# Physio_v1_0.net
KiCad netlist of a schematic drawn in EAGLE
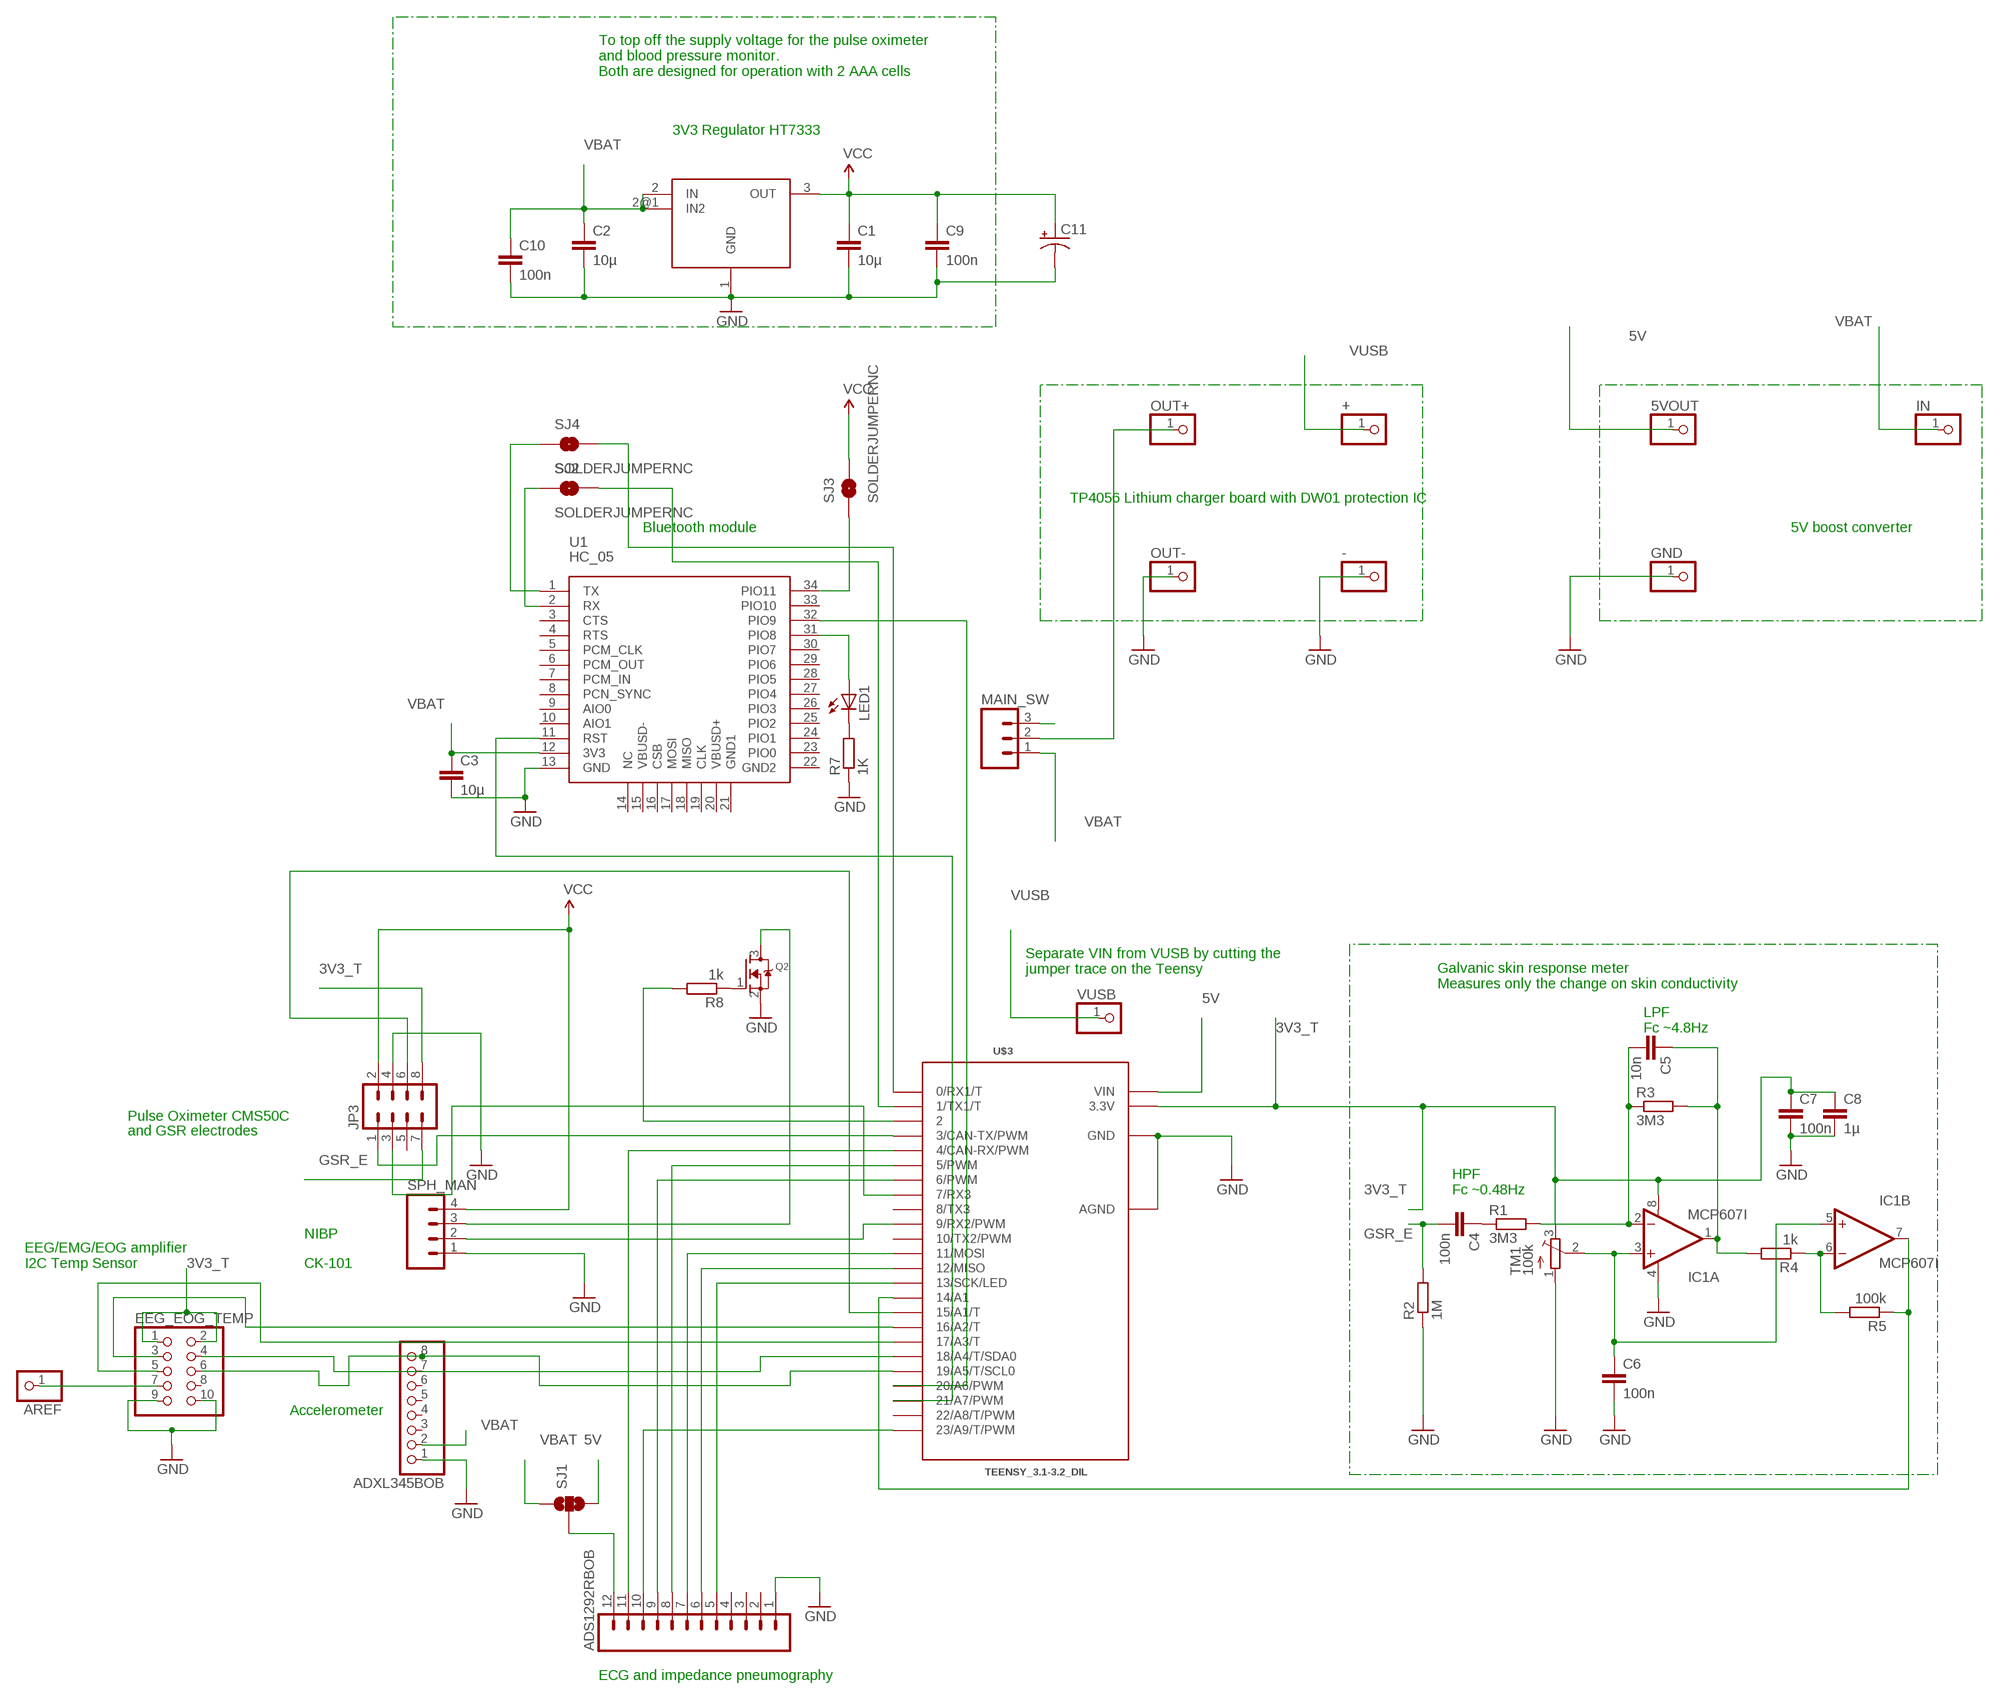
[diagram p0: schematic, sheet 1]

(export (version "E")
  (design (tool "Eeschema 10.0.6"))
  (components
    (comp (ref "+")
      (value "PINHD-1X1")
      (footprint "eagle-import:1X01")
      (libsource (lib "eagle-import") (part "PINHD-1X1"))
    )
    (comp (ref "-")
      (value "PINHD-1X1")
      (footprint "eagle-import:1X01")
      (libsource (lib "eagle-import") (part "PINHD-1X1"))
    )
    (comp (ref "5VOUT")
      (value "PINHD-1X1")
      (footprint "eagle-import:1X01")
      (libsource (lib "eagle-import") (part "PINHD-1X1"))
    )
    (comp (ref "ADS1292RBOB")
      (value "M12PTH")
      (footprint "eagle-import:1X12")
      (libsource (lib "eagle-import") (part "M12PTH"))
    )
    (comp (ref "ADXL345BOB")
      (value "PINHD-1X8CLEANBIG")
      (footprint "eagle-import:1X08-CLEANBIG")
      (libsource (lib "eagle-import") (part "PINHD-1X8CLEANBIG"))
    )
    (comp (ref "AREF")
      (value "PINHD-1X1")
      (footprint "eagle-import:1X01")
      (libsource (lib "eagle-import") (part "pinhead_PINHD-1X1"))
    )
    (comp (ref "C1")
      (value "10µ")
      (footprint "eagle-import:C0805K")
      (libsource (lib "eagle-import") (part "C-EUC0805K"))
    )
    (comp (ref "C2")
      (value "10µ")
      (footprint "eagle-import:C0805K")
      (libsource (lib "eagle-import") (part "C-EUC0805K"))
    )
    (comp (ref "C3")
      (value "10µ")
      (footprint "eagle-import:C0805K")
      (libsource (lib "eagle-import") (part "C-EUC0805K"))
    )
    (comp (ref "C4")
      (value "100n")
      (footprint "eagle-import:C0603K")
      (libsource (lib "eagle-import") (part "C-EUC0603K"))
    )
    (comp (ref "C5")
      (value "10n")
      (footprint "eagle-import:C0603K")
      (libsource (lib "eagle-import") (part "C-EUC0603K"))
    )
    (comp (ref "C6")
      (value "100n")
      (footprint "eagle-import:C0603K")
      (libsource (lib "eagle-import") (part "C-EUC0603K"))
    )
    (comp (ref "C7")
      (value "100n")
      (footprint "eagle-import:C0603K")
      (libsource (lib "eagle-import") (part "C-EUC0603K"))
    )
    (comp (ref "C8")
      (value "1µ")
      (footprint "eagle-import:C0603K")
      (libsource (lib "eagle-import") (part "C-EUC0603K"))
    )
    (comp (ref "C9")
      (value "100n")
      (footprint "eagle-import:C0603K")
      (libsource (lib "eagle-import") (part "C-EUC0603K"))
    )
    (comp (ref "C10")
      (value "100n")
      (footprint "eagle-import:C0603K")
      (libsource (lib "eagle-import") (part "C-EUC0603K"))
    )
    (comp (ref "C11")
      (value "CAP_POL7343")
      (footprint "eagle-import:EIA7343")
      (libsource (lib "eagle-import") (part "CAP_POL7343"))
    )
    (comp (ref "EEG_EOG_TEMP")
      (value "PINHD-2X5/90")
      (footprint "eagle-import:2X05_90")
      (libsource (lib "eagle-import") (part "PINHD-2X5/90"))
    )
    (comp (ref "GND")
      (value "PINHD-1X1")
      (footprint "eagle-import:1X01")
      (libsource (lib "eagle-import") (part "PINHD-1X1"))
    )
    (comp (ref "IC1")
      (value "MCP607I")
      (footprint "eagle-import:SO08")
      (libsource (lib "eagle-import") (part "OPAMP-DUALU"))
    )
    (comp (ref "IN")
      (value "PINHD-1X1")
      (footprint "eagle-import:1X01")
      (libsource (lib "eagle-import") (part "PINHD-1X1"))
    )
    (comp (ref "JP3")
      (value "M04X2")
      (footprint "eagle-import:2X4")
      (libsource (lib "eagle-import") (part "M04X2"))
    )
    (comp (ref "LED1")
      (value "LEDCHIP-LED0805")
      (footprint "eagle-import:CHIP-LED0805")
      (libsource (lib "eagle-import") (part "LEDCHIP-LED0805"))
    )
    (comp (ref "MAIN_SW")
      (value "M03PTH")
      (footprint "eagle-import:1X03")
      (libsource (lib "eagle-import") (part "M03PTH"))
    )
    (comp (ref "OUT+")
      (value "PINHD-1X1")
      (footprint "eagle-import:1X01")
      (libsource (lib "eagle-import") (part "PINHD-1X1"))
    )
    (comp (ref "OUT-")
      (value "PINHD-1X1")
      (footprint "eagle-import:1X01")
      (libsource (lib "eagle-import") (part "PINHD-1X1"))
    )
    (comp (ref "Q2")
      (value "MOSFET-NREFLOW")
      (footprint "eagle-import:SOT23")
      (libsource (lib "eagle-import") (part "MOSFET-NREFLOW"))
    )
    (comp (ref "R1")
      (value "3M3")
      (footprint "eagle-import:R0603")
      (libsource (lib "eagle-import") (part "R-EU_R0603"))
    )
    (comp (ref "R2")
      (value "1M")
      (footprint "eagle-import:R0603")
      (libsource (lib "eagle-import") (part "R-EU_R0603"))
    )
    (comp (ref "R3")
      (value "3M3")
      (footprint "eagle-import:R0603")
      (libsource (lib "eagle-import") (part "R-EU_R0603"))
    )
    (comp (ref "R4")
      (value "1k")
      (footprint "eagle-import:R0603")
      (libsource (lib "eagle-import") (part "R-EU_R0603"))
    )
    (comp (ref "R5")
      (value "100k")
      (footprint "eagle-import:R0603")
      (libsource (lib "eagle-import") (part "R-EU_R0603"))
    )
    (comp (ref "R7")
      (value "1K")
      (footprint "eagle-import:R0603")
      (libsource (lib "eagle-import") (part "R-EU_R0603"))
    )
    (comp (ref "R8")
      (value "1k")
      (footprint "eagle-import:R0603")
      (libsource (lib "eagle-import") (part "R-EU_R0603"))
    )
    (comp (ref "SJ1")
      (value "SOLDERJUMPER_2WAY-OLDT")
      (footprint "eagle-import:SJ_2")
      (libsource (lib "eagle-import") (part "SOLDERJUMPER_2WAY-OLDT"))
    )
    (comp (ref "SJ2")
      (value "SOLDERJUMPERNC")
      (footprint "eagle-import:SJ_2S")
      (libsource (lib "eagle-import") (part "SOLDERJUMPERNC"))
    )
    (comp (ref "SJ3")
      (value "SOLDERJUMPERNC")
      (footprint "eagle-import:SJ_2S")
      (libsource (lib "eagle-import") (part "SOLDERJUMPERNC"))
    )
    (comp (ref "SJ4")
      (value "SOLDERJUMPERNC")
      (footprint "eagle-import:SJ_2S")
      (libsource (lib "eagle-import") (part "SOLDERJUMPERNC"))
    )
    (comp (ref "SPH_MAN")
      (value "M04PTH")
      (footprint "eagle-import:1X04")
      (libsource (lib "eagle-import") (part "M04PTH"))
    )
    (comp (ref "TM1")
      (value "100k")
      (footprint "eagle-import:TC33X")
      (libsource (lib "eagle-import") (part "TRIMPOTTC33X"))
    )
    (comp (ref "U$2")
      (value "HT7333")
      (footprint "eagle-import:SOT89")
      (libsource (lib "eagle-import") (part "HT7333"))
    )
    (comp (ref "U$3")
      (value "TEENSY_3.1-3.2_DIL")
      (footprint "eagle-import:TEENSY_3.0-3.2&LC_DIL")
      (libsource (lib "eagle-import") (part "TEENSY_3.1-3.2_DIL"))
    )
    (comp (ref "U1")
      (value "HC_05")
      (footprint "eagle-import:BLUETOOTH_SMD")
      (libsource (lib "eagle-import") (part "HC_05"))
    )
    (comp (ref "VUSB")
      (value "PINHD-1X1")
      (footprint "eagle-import:1X01")
      (libsource (lib "eagle-import") (part "PINHD-1X1"))
    )
  )
  (nets
    (net (code "1") (name "/3V3_T") (class "Default")
      (node (ref "C7") (pin "1") (pinfunction "1_1") (pintype "passive"))
      (node (ref "C8") (pin "1") (pinfunction "1_1") (pintype "passive"))
      (node (ref "EEG_EOG_TEMP") (pin "1") (pinfunction "1_1") (pintype "passive"))
      (node (ref "EEG_EOG_TEMP") (pin "2") (pinfunction "2_2") (pintype "passive"))
      (node (ref "IC1") (pin "8") (pinfunction "V+_8") (pintype "power_in"))
      (node (ref "JP3") (pin "8") (pinfunction "8_8") (pintype "passive"))
      (node (ref "TM1") (pin "3") (pinfunction "E_3") (pintype "passive"))
      (node (ref "U$3") (pin "3.3V") (pinfunction "3.3V_3.3V") (pintype "power_in"))
    )
    (net (code "2") (name "/5V") (class "Default")
      (node (ref "5VOUT") (pin "1") (pinfunction "1_1") (pintype "passive"))
      (node (ref "SJ1") (pin "3") (pinfunction "3_3") (pintype "passive"))
      (node (ref "U$3") (pin "VIN") (pinfunction "VIN_VIN") (pintype "power_in"))
    )
    (net (code "3") (name "/GSR_E") (class "Default")
      (node (ref "C4") (pin "2") (pinfunction "2_2") (pintype "passive"))
      (node (ref "JP3") (pin "7") (pinfunction "7_7") (pintype "passive"))
      (node (ref "R2") (pin "2") (pinfunction "2_2") (pintype "passive"))
    )
    (net (code "5") (name "/VBAT") (class "Default")
      (node (ref "ADXL345BOB") (pin "2") (pinfunction "2_2") (pintype "passive"))
      (node (ref "C10") (pin "1") (pinfunction "1_1") (pintype "passive"))
      (node (ref "C2") (pin "1") (pinfunction "1_1") (pintype "passive"))
      (node (ref "C3") (pin "1") (pinfunction "1_1") (pintype "passive"))
      (node (ref "IN") (pin "1") (pinfunction "1_1") (pintype "passive"))
      (node (ref "MAIN_SW") (pin "1") (pinfunction "1_1") (pintype "passive"))
      (node (ref "SJ1") (pin "1") (pinfunction "1_1") (pintype "passive"))
      (node (ref "U$2") (pin "2") (pinfunction "IN_2") (pintype "bidirectional"))
      (node (ref "U$2") (pin "2@1") (pinfunction "IN2_2@1") (pintype "bidirectional"))
      (node (ref "U1") (pin "12") (pinfunction "3V3_12") (pintype "bidirectional"))
    )
    (net (code "6") (name "/VUSB") (class "Default")
      (node (ref "+") (pin "1") (pinfunction "1_1") (pintype "passive"))
      (node (ref "VUSB") (pin "1") (pinfunction "1_1") (pintype "passive"))
    )
    (net (code "7") (name "GND") (class "Default")
      (node (ref "-") (pin "1") (pinfunction "1_1") (pintype "passive"))
      (node (ref "ADS1292RBOB") (pin "1") (pinfunction "1_1") (pintype "passive"))
      (node (ref "ADXL345BOB") (pin "1") (pinfunction "1_1") (pintype "passive"))
      (node (ref "C1") (pin "2") (pinfunction "2_2") (pintype "passive"))
      (node (ref "C10") (pin "2") (pinfunction "2_2") (pintype "passive"))
      (node (ref "C11") (pin "C") (pinfunction "-_C") (pintype "passive"))
      (node (ref "C2") (pin "2") (pinfunction "2_2") (pintype "passive"))
      (node (ref "C3") (pin "2") (pinfunction "2_2") (pintype "passive"))
      (node (ref "C6") (pin "2") (pinfunction "2_2") (pintype "passive"))
      (node (ref "C7") (pin "2") (pinfunction "2_2") (pintype "passive"))
      (node (ref "C8") (pin "2") (pinfunction "2_2") (pintype "passive"))
      (node (ref "C9") (pin "2") (pinfunction "2_2") (pintype "passive"))
      (node (ref "EEG_EOG_TEMP") (pin "10") (pinfunction "10_10") (pintype "passive"))
      (node (ref "EEG_EOG_TEMP") (pin "9") (pinfunction "9_9") (pintype "passive"))
      (node (ref "GND") (pin "1") (pinfunction "1_1") (pintype "passive"))
      (node (ref "IC1") (pin "4") (pinfunction "V-_4") (pintype "power_in"))
      (node (ref "JP3") (pin "4") (pinfunction "4_4") (pintype "passive"))
      (node (ref "OUT-") (pin "1") (pinfunction "1_1") (pintype "passive"))
      (node (ref "Q2") (pin "2") (pinfunction "S_2") (pintype "bidirectional"))
      (node (ref "R2") (pin "1") (pinfunction "1_1") (pintype "passive"))
      (node (ref "R7") (pin "1") (pinfunction "1_1") (pintype "passive"))
      (node (ref "SPH_MAN") (pin "1") (pinfunction "1_1") (pintype "passive"))
      (node (ref "TM1") (pin "1") (pinfunction "A_1") (pintype "passive"))
      (node (ref "U$2") (pin "1") (pinfunction "GND_1") (pintype "bidirectional"))
      (node (ref "U$3") (pin "AGND") (pinfunction "AGND_AGND") (pintype "power_in"))
      (node (ref "U$3") (pin "GND") (pinfunction "GND_GND") (pintype "power_in"))
      (node (ref "U1") (pin "13") (pinfunction "GND_13") (pintype "bidirectional"))
    )
    (net (code "8") (name "Net-(ADS1292RBOB-Pad12)") (class "Default")
      (node (ref "ADS1292RBOB") (pin "12") (pinfunction "12_12") (pintype "passive"))
      (node (ref "SJ1") (pin "2") (pinfunction "2_2") (pintype "passive"))
    )
    (net (code "9") (name "Net-(AREF-Pad1)") (class "Default")
      (node (ref "AREF") (pin "1") (pinfunction "1_1") (pintype "passive"))
      (node (ref "EEG_EOG_TEMP") (pin "7") (pinfunction "7_7") (pintype "passive"))
    )
    (net (code "10") (name "Net-(C4-Pad1)") (class "Default")
      (node (ref "C4") (pin "1") (pinfunction "1_1") (pintype "passive"))
      (node (ref "R1") (pin "1") (pinfunction "1_1") (pintype "passive"))
    )
    (net (code "11") (name "Net-(IC1A-+IN)") (class "Default")
      (node (ref "C6") (pin "1") (pinfunction "1_1") (pintype "passive"))
      (node (ref "IC1") (pin "3") (pinfunction "+IN_3") (pintype "input"))
      (node (ref "IC1") (pin "5") (pinfunction "+IN_5") (pintype "input"))
      (node (ref "TM1") (pin "2") (pinfunction "S_2") (pintype "passive"))
    )
    (net (code "12") (name "Net-(IC1A--IN)") (class "Default")
      (node (ref "C5") (pin "2") (pinfunction "2_2") (pintype "passive"))
      (node (ref "IC1") (pin "2") (pinfunction "-IN_2") (pintype "input"))
      (node (ref "R1") (pin "2") (pinfunction "2_2") (pintype "passive"))
      (node (ref "R3") (pin "1") (pinfunction "1_1") (pintype "passive"))
    )
    (net (code "13") (name "Net-(IC1A-OUT)") (class "Default")
      (node (ref "C5") (pin "1") (pinfunction "1_1") (pintype "passive"))
      (node (ref "IC1") (pin "1") (pinfunction "OUT_1") (pintype "output"))
      (node (ref "R3") (pin "2") (pinfunction "2_2") (pintype "passive"))
      (node (ref "R4") (pin "2") (pinfunction "2_2") (pintype "passive"))
    )
    (net (code "14") (name "Net-(IC1B--IN)") (class "Default")
      (node (ref "IC1") (pin "6") (pinfunction "-IN_6") (pintype "input"))
      (node (ref "R4") (pin "1") (pinfunction "1_1") (pintype "passive"))
      (node (ref "R5") (pin "2") (pinfunction "2_2") (pintype "passive"))
    )
    (net (code "15") (name "Net-(IC1B-OUT)") (class "Default")
      (node (ref "IC1") (pin "7") (pinfunction "OUT_7") (pintype "output"))
      (node (ref "R5") (pin "1") (pinfunction "1_1") (pintype "passive"))
      (node (ref "U$3") (pin "14/A0") (pinfunction "14/A1_14/A0") (pintype "bidirectional"))
    )
    (net (code "16") (name "Net-(LED1-PadC)") (class "Default")
      (node (ref "LED1") (pin "C") (pinfunction "C_C") (pintype "passive"))
      (node (ref "R7") (pin "2") (pinfunction "2_2") (pintype "passive"))
    )
    (net (code "17") (name "Net-(MAIN_SW-Pad2)") (class "Default")
      (node (ref "MAIN_SW") (pin "2") (pinfunction "2_2") (pintype "passive"))
      (node (ref "OUT+") (pin "1") (pinfunction "1_1") (pintype "passive"))
    )
    (net (code "18") (name "Net-(Q2-D)") (class "Default")
      (node (ref "Q2") (pin "3") (pinfunction "D_3") (pintype "bidirectional"))
      (node (ref "SPH_MAN") (pin "3") (pinfunction "3_3") (pintype "passive"))
    )
    (net (code "19") (name "Net-(Q2-G)") (class "Default")
      (node (ref "Q2") (pin "1") (pinfunction "G_1") (pintype "bidirectional"))
      (node (ref "R8") (pin "1") (pinfunction "1_1") (pintype "passive"))
    )
    (net (code "20") (name "Net-(R8-Pad2)") (class "Default")
      (node (ref "R8") (pin "2") (pinfunction "2_2") (pintype "passive"))
      (node (ref "U$3") (pin "2") (pinfunction "2_2") (pintype "bidirectional"))
    )
    (net (code "21") (name "Net-(U$3-0{slash}RX1{slash}T)") (class "Default")
      (node (ref "SJ4") (pin "2") (pinfunction "2_2") (pintype "passive"))
      (node (ref "U$3") (pin "0") (pinfunction "0/RX1/T_0") (pintype "bidirectional"))
    )
    (net (code "22") (name "Net-(U$3-1{slash}TX1{slash}T)") (class "Default")
      (node (ref "SJ2") (pin "2") (pinfunction "2_2") (pintype "passive"))
      (node (ref "U$3") (pin "1") (pinfunction "1/TX1/T_1") (pintype "bidirectional"))
    )
    (net (code "23") (name "Net-(U$3-3{slash}CAN-TX{slash}PWM)") (class "Default")
      (node (ref "JP3") (pin "1") (pinfunction "1_1") (pintype "passive"))
      (node (ref "U$3") (pin "3") (pinfunction "3/CAN-TX/PWM_3") (pintype "bidirectional"))
    )
    (net (code "24") (name "Net-(U$3-4{slash}CAN-RX{slash}PWM)") (class "Default")
      (node (ref "ADS1292RBOB") (pin "11") (pinfunction "11_11") (pintype "passive"))
      (node (ref "U$3") (pin "4") (pinfunction "4/CAN-RX/PWM_4") (pintype "bidirectional"))
    )
    (net (code "25") (name "Net-(U$3-5{slash}PWM)") (class "Default")
      (node (ref "ADS1292RBOB") (pin "8") (pinfunction "8_8") (pintype "passive"))
      (node (ref "U$3") (pin "5") (pinfunction "5/PWM_5") (pintype "bidirectional"))
    )
    (net (code "26") (name "Net-(U$3-6{slash}PWM)") (class "Default")
      (node (ref "ADS1292RBOB") (pin "9") (pinfunction "9_9") (pintype "passive"))
      (node (ref "U$3") (pin "6") (pinfunction "6/PWM_6") (pintype "bidirectional"))
    )
    (net (code "27") (name "Net-(U$3-7{slash}RX3)") (class "Default")
      (node (ref "JP3") (pin "3") (pinfunction "3_3") (pintype "passive"))
      (node (ref "U$3") (pin "7") (pinfunction "7/RX3_7") (pintype "bidirectional"))
    )
    (net (code "28") (name "Net-(U$3-9{slash}RX2{slash}PWM)") (class "Default")
      (node (ref "SPH_MAN") (pin "2") (pinfunction "2_2") (pintype "passive"))
      (node (ref "U$3") (pin "9") (pinfunction "9/RX2/PWM_9") (pintype "bidirectional"))
    )
    (net (code "29") (name "Net-(U$3-11{slash}MOSI)") (class "Default")
      (node (ref "ADS1292RBOB") (pin "7") (pinfunction "7_7") (pintype "passive"))
      (node (ref "U$3") (pin "11") (pinfunction "11/MOSI_11") (pintype "bidirectional"))
    )
    (net (code "30") (name "Net-(U$3-12{slash}MISO)") (class "Default")
      (node (ref "ADS1292RBOB") (pin "6") (pinfunction "6_6") (pintype "passive"))
      (node (ref "U$3") (pin "12") (pinfunction "12/MISO_12") (pintype "bidirectional"))
    )
    (net (code "31") (name "Net-(U$3-13{slash}SCK{slash}LED)") (class "Default")
      (node (ref "ADS1292RBOB") (pin "5") (pinfunction "5_5") (pintype "passive"))
      (node (ref "U$3") (pin "13") (pinfunction "13/SCK/LED_13") (pintype "bidirectional"))
    )
    (net (code "32") (name "Net-(U$3-15{slash}A1{slash}T)") (class "Default")
      (node (ref "JP3") (pin "6") (pinfunction "6_6") (pintype "passive"))
      (node (ref "U$3") (pin "15/A1") (pinfunction "15/A1/T_15/A1") (pintype "bidirectional"))
    )
    (net (code "33") (name "Net-(U$3-16{slash}A2{slash}T)") (class "Default")
      (node (ref "EEG_EOG_TEMP") (pin "3") (pinfunction "3_3") (pintype "passive"))
      (node (ref "U$3") (pin "16/A2") (pinfunction "16/A2/T_16/A2") (pintype "bidirectional"))
    )
    (net (code "34") (name "Net-(U$3-17{slash}A3{slash}T)") (class "Default")
      (node (ref "EEG_EOG_TEMP") (pin "5") (pinfunction "5_5") (pintype "passive"))
      (node (ref "U$3") (pin "17/A3") (pinfunction "17/A3/T_17/A3") (pintype "bidirectional"))
    )
    (net (code "35") (name "Net-(U$3-18{slash}A4{slash}T{slash}SDA0)") (class "Default")
      (node (ref "ADXL345BOB") (pin "7") (pinfunction "7_7") (pintype "passive"))
      (node (ref "EEG_EOG_TEMP") (pin "4") (pinfunction "4_4") (pintype "passive"))
      (node (ref "U$3") (pin "18/A4") (pinfunction "18/A4/T/SDA0_18/A4") (pintype "bidirectional"))
    )
    (net (code "36") (name "Net-(U$3-19{slash}A5{slash}T{slash}SCL0)") (class "Default")
      (node (ref "ADXL345BOB") (pin "8") (pinfunction "8_8") (pintype "passive"))
      (node (ref "EEG_EOG_TEMP") (pin "6") (pinfunction "6_6") (pintype "passive"))
      (node (ref "U$3") (pin "19/A5") (pinfunction "19/A5/T/SCL0_19/A5") (pintype "bidirectional"))
    )
    (net (code "37") (name "Net-(U$3-20{slash}A6{slash}PWM)") (class "Default")
      (node (ref "U$3") (pin "20/A6") (pinfunction "20/A6/PWM_20/A6") (pintype "bidirectional"))
      (node (ref "U1") (pin "32") (pinfunction "PIO9_32") (pintype "bidirectional"))
    )
    (net (code "38") (name "Net-(U$3-21{slash}A7{slash}PWM)") (class "Default")
      (node (ref "U$3") (pin "21/A7") (pinfunction "21/A7/PWM_21/A7") (pintype "bidirectional"))
      (node (ref "U1") (pin "11") (pinfunction "RST_11") (pintype "bidirectional"))
    )
    (net (code "39") (name "Net-(U$3-23{slash}A9{slash}T{slash}PWM)") (class "Default")
      (node (ref "ADS1292RBOB") (pin "10") (pinfunction "10_10") (pintype "passive"))
      (node (ref "U$3") (pin "23/A9") (pinfunction "23/A9/T/PWM_23/A9") (pintype "bidirectional"))
    )
    (net (code "40") (name "Net-(U1-PIO8)") (class "Default")
      (node (ref "LED1") (pin "A") (pinfunction "A_A") (pintype "passive"))
      (node (ref "U1") (pin "31") (pinfunction "PIO8_31") (pintype "bidirectional"))
    )
    (net (code "41") (name "Net-(U1-PIO11)") (class "Default")
      (node (ref "SJ3") (pin "1") (pinfunction "1_1") (pintype "passive"))
      (node (ref "U1") (pin "34") (pinfunction "PIO11_34") (pintype "bidirectional"))
    )
    (net (code "42") (name "Net-(U1-RX)") (class "Default")
      (node (ref "SJ2") (pin "1") (pinfunction "1_1") (pintype "passive"))
      (node (ref "U1") (pin "2") (pinfunction "RX_2") (pintype "bidirectional"))
    )
    (net (code "43") (name "Net-(U1-TX)") (class "Default")
      (node (ref "SJ4") (pin "1") (pinfunction "1_1") (pintype "passive"))
      (node (ref "U1") (pin "1") (pinfunction "TX_1") (pintype "bidirectional"))
    )
    (net (code "44") (name "VCC") (class "Default")
      (node (ref "C1") (pin "1") (pinfunction "1_1") (pintype "passive"))
      (node (ref "C11") (pin "A") (pinfunction "+_A") (pintype "passive"))
      (node (ref "C9") (pin "1") (pinfunction "1_1") (pintype "passive"))
      (node (ref "JP3") (pin "2") (pinfunction "2_2") (pintype "passive"))
      (node (ref "SJ3") (pin "2") (pinfunction "2_2") (pintype "passive"))
      (node (ref "SPH_MAN") (pin "4") (pinfunction "4_4") (pintype "passive"))
      (node (ref "U$2") (pin "3") (pinfunction "OUT_3") (pintype "bidirectional"))
    )
    (net (code "45") (name "unconnected-(ADS1292RBOB-Pad2)") (class "Default")
      (node (ref "ADS1292RBOB") (pin "2") (pinfunction "2_2") (pintype "passive"))
    )
    (net (code "46") (name "unconnected-(ADS1292RBOB-Pad3)") (class "Default")
      (node (ref "ADS1292RBOB") (pin "3") (pinfunction "3_3") (pintype "passive"))
    )
    (net (code "47") (name "unconnected-(ADS1292RBOB-Pad4)") (class "Default")
      (node (ref "ADS1292RBOB") (pin "4") (pinfunction "4_4") (pintype "passive"))
    )
    (net (code "48") (name "unconnected-(ADXL345BOB-Pad3)") (class "Default")
      (node (ref "ADXL345BOB") (pin "3") (pinfunction "3_3") (pintype "passive"))
    )
    (net (code "49") (name "unconnected-(ADXL345BOB-Pad4)") (class "Default")
      (node (ref "ADXL345BOB") (pin "4") (pinfunction "4_4") (pintype "passive"))
    )
    (net (code "50") (name "unconnected-(ADXL345BOB-Pad5)") (class "Default")
      (node (ref "ADXL345BOB") (pin "5") (pinfunction "5_5") (pintype "passive"))
    )
    (net (code "51") (name "unconnected-(ADXL345BOB-Pad6)") (class "Default")
      (node (ref "ADXL345BOB") (pin "6") (pinfunction "6_6") (pintype "passive"))
    )
    (net (code "52") (name "unconnected-(EEG_EOG_TEMP-Pad8)") (class "Default")
      (node (ref "EEG_EOG_TEMP") (pin "8") (pinfunction "8_8") (pintype "passive"))
    )
    (net (code "53") (name "unconnected-(JP3-Pad5)") (class "Default")
      (node (ref "JP3") (pin "5") (pinfunction "5_5") (pintype "passive"))
    )
    (net (code "54") (name "unconnected-(MAIN_SW-Pad3)") (class "Default")
      (node (ref "MAIN_SW") (pin "3") (pinfunction "3_3") (pintype "passive"))
    )
    (net (code "55") (name "unconnected-(U$3-8{slash}TX3-Pad8)") (class "Default")
      (node (ref "U$3") (pin "8") (pinfunction "8/TX3_8") (pintype "bidirectional"))
    )
    (net (code "56") (name "unconnected-(U$3-10{slash}TX2{slash}PWM-Pad10)") (class "Default")
      (node (ref "U$3") (pin "10") (pinfunction "10/TX2/PWM_10") (pintype "bidirectional"))
    )
    (net (code "57") (name "unconnected-(U$3-22{slash}A8{slash}T{slash}PWM-Pad22{slash}A8)") (class "Default")
      (node (ref "U$3") (pin "22/A8") (pinfunction "22/A8/T/PWM_22/A8") (pintype "bidirectional"))
    )
    (net (code "58") (name "unconnected-(U1-AIO0-Pad9)") (class "Default")
      (node (ref "U1") (pin "9") (pinfunction "AIO0_9") (pintype "bidirectional"))
    )
    (net (code "59") (name "unconnected-(U1-AIO1-Pad10)") (class "Default")
      (node (ref "U1") (pin "10") (pinfunction "AIO1_10") (pintype "bidirectional"))
    )
    (net (code "60") (name "unconnected-(U1-CLK-Pad19)") (class "Default")
      (node (ref "U1") (pin "19") (pinfunction "CLK_19") (pintype "bidirectional"))
    )
    (net (code "61") (name "unconnected-(U1-CSB-Pad16)") (class "Default")
      (node (ref "U1") (pin "16") (pinfunction "CSB_16") (pintype "bidirectional"))
    )
    (net (code "62") (name "unconnected-(U1-CTS-Pad3)") (class "Default")
      (node (ref "U1") (pin "3") (pinfunction "CTS_3") (pintype "bidirectional"))
    )
    (net (code "63") (name "unconnected-(U1-GND1-Pad21)") (class "Default")
      (node (ref "U1") (pin "21") (pinfunction "GND1_21") (pintype "bidirectional"))
    )
    (net (code "64") (name "unconnected-(U1-GND2-Pad22)") (class "Default")
      (node (ref "U1") (pin "22") (pinfunction "GND2_22") (pintype "bidirectional"))
    )
    (net (code "65") (name "unconnected-(U1-MISO-Pad18)") (class "Default")
      (node (ref "U1") (pin "18") (pinfunction "MISO_18") (pintype "bidirectional"))
    )
    (net (code "66") (name "unconnected-(U1-MOSI-Pad17)") (class "Default")
      (node (ref "U1") (pin "17") (pinfunction "MOSI_17") (pintype "bidirectional"))
    )
    (net (code "67") (name "unconnected-(U1-NC-Pad14)") (class "Default")
      (node (ref "U1") (pin "14") (pinfunction "NC_14") (pintype "bidirectional"))
    )
    (net (code "68") (name "unconnected-(U1-PCM_CLK-Pad5)") (class "Default")
      (node (ref "U1") (pin "5") (pinfunction "PCM_CLK_5") (pintype "bidirectional"))
    )
    (net (code "69") (name "unconnected-(U1-PCM_IN-Pad7)") (class "Default")
      (node (ref "U1") (pin "7") (pinfunction "PCM_IN_7") (pintype "bidirectional"))
    )
    (net (code "70") (name "unconnected-(U1-PCM_OUT-Pad6)") (class "Default")
      (node (ref "U1") (pin "6") (pinfunction "PCM_OUT_6") (pintype "bidirectional"))
    )
    (net (code "71") (name "unconnected-(U1-PCN_SYNC-Pad8)") (class "Default")
      (node (ref "U1") (pin "8") (pinfunction "PCN_SYNC_8") (pintype "bidirectional"))
    )
    (net (code "72") (name "unconnected-(U1-PIO0-Pad23)") (class "Default")
      (node (ref "U1") (pin "23") (pinfunction "PIO0_23") (pintype "bidirectional"))
    )
    (net (code "73") (name "unconnected-(U1-PIO1-Pad24)") (class "Default")
      (node (ref "U1") (pin "24") (pinfunction "PIO1_24") (pintype "bidirectional"))
    )
    (net (code "74") (name "unconnected-(U1-PIO2-Pad25)") (class "Default")
      (node (ref "U1") (pin "25") (pinfunction "PIO2_25") (pintype "bidirectional"))
    )
    (net (code "75") (name "unconnected-(U1-PIO3-Pad26)") (class "Default")
      (node (ref "U1") (pin "26") (pinfunction "PIO3_26") (pintype "bidirectional"))
    )
    (net (code "76") (name "unconnected-(U1-PIO4-Pad27)") (class "Default")
      (node (ref "U1") (pin "27") (pinfunction "PIO4_27") (pintype "bidirectional"))
    )
    (net (code "77") (name "unconnected-(U1-PIO5-Pad28)") (class "Default")
      (node (ref "U1") (pin "28") (pinfunction "PIO5_28") (pintype "bidirectional"))
    )
    (net (code "78") (name "unconnected-(U1-PIO6-Pad29)") (class "Default")
      (node (ref "U1") (pin "29") (pinfunction "PIO6_29") (pintype "bidirectional"))
    )
    (net (code "79") (name "unconnected-(U1-PIO7-Pad30)") (class "Default")
      (node (ref "U1") (pin "30") (pinfunction "PIO7_30") (pintype "bidirectional"))
    )
    (net (code "80") (name "unconnected-(U1-PIO10-Pad33)") (class "Default")
      (node (ref "U1") (pin "33") (pinfunction "PIO10_33") (pintype "bidirectional"))
    )
    (net (code "81") (name "unconnected-(U1-RTS-Pad4)") (class "Default")
      (node (ref "U1") (pin "4") (pinfunction "RTS_4") (pintype "bidirectional"))
    )
    (net (code "82") (name "unconnected-(U1-VBUSD+-Pad20)") (class "Default")
      (node (ref "U1") (pin "20") (pinfunction "VBUSD+_20") (pintype "bidirectional"))
    )
    (net (code "83") (name "unconnected-(U1-VBUSD--Pad15)") (class "Default")
      (node (ref "U1") (pin "15") (pinfunction "VBUSD-_15") (pintype "bidirectional"))
    )
  )
)
